# powersupplyboard.net
KiCad netlist of a schematic drawn in EAGLE
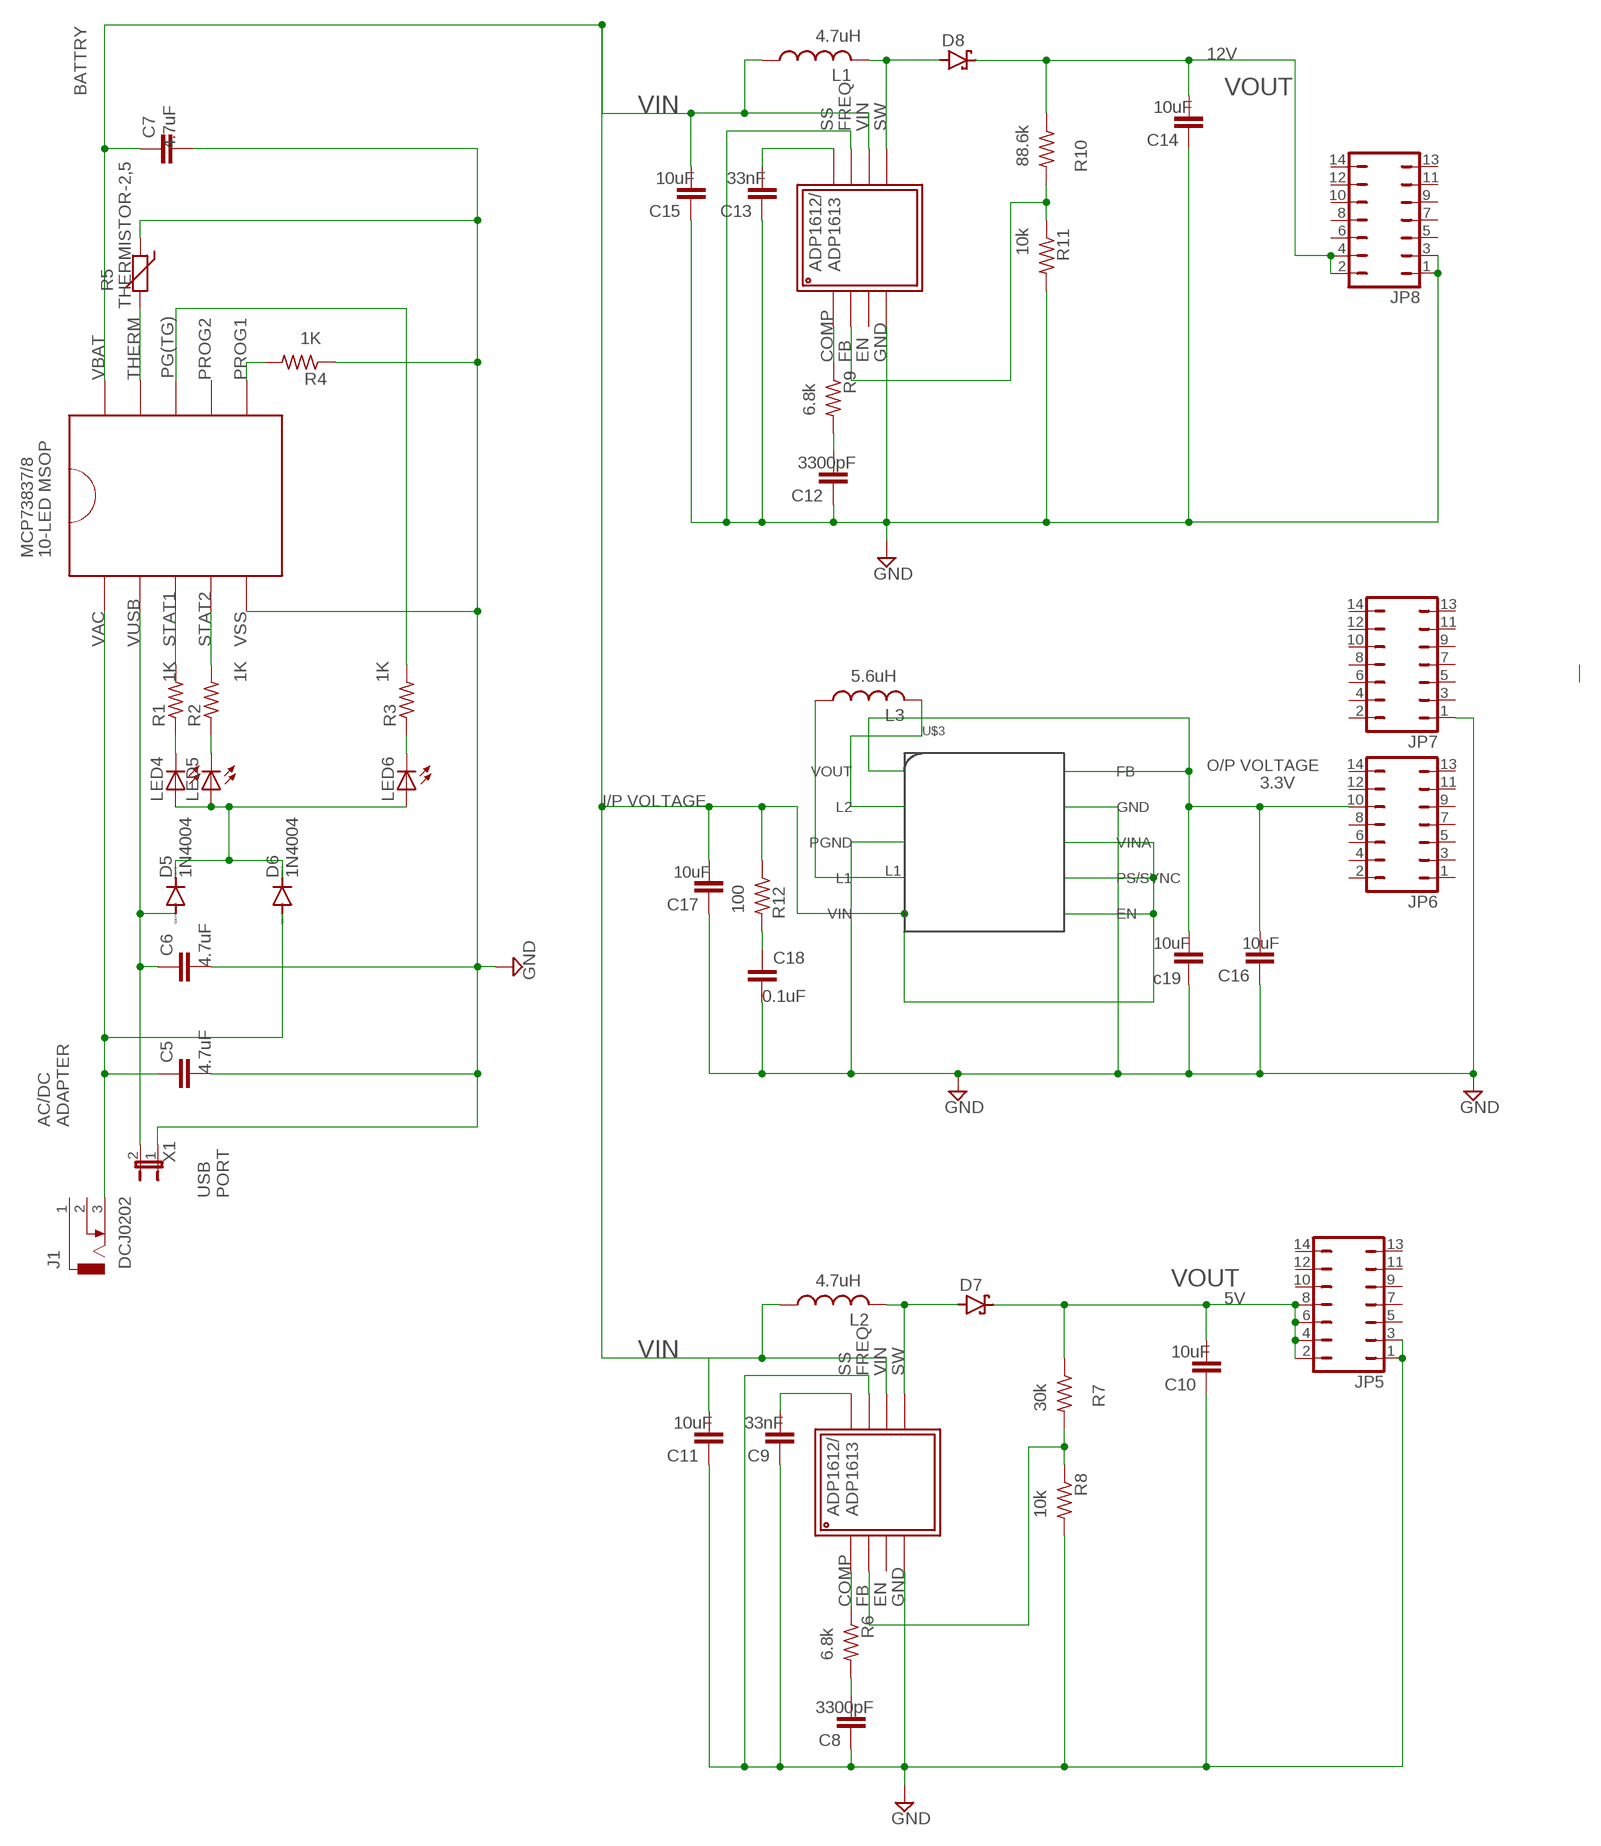
[diagram p0: schematic, sheet 1]

(export (version "E")
  (design (tool "Eeschema 10.0.6"))
  (components
    (comp (ref "C1")
      (value "C2,5-3")
      (footprint "eagle-import:C2.5-3")
      (libsource (lib "eagle-import") (part "C2,5-3"))
    )
    (comp (ref "C5")
      (value "C2.5/5")
      (footprint "eagle-import:C2.5-5")
      (libsource (lib "eagle-import") (part "C2.5/5"))
    )
    (comp (ref "C6")
      (value "C2.5/5")
      (footprint "eagle-import:C2.5-5")
      (libsource (lib "eagle-import") (part "C2.5/5"))
    )
    (comp (ref "C7")
      (value "C2.5/5")
      (footprint "eagle-import:C2.5-5")
      (libsource (lib "eagle-import") (part "C2.5/5"))
    )
    (comp (ref "C8")
      (value "C2,5-3")
      (footprint "eagle-import:C2.5-3")
      (libsource (lib "eagle-import") (part "C2,5-3"))
    )
    (comp (ref "C9")
      (value "C2,5-3")
      (footprint "eagle-import:C2.5-3")
      (libsource (lib "eagle-import") (part "C2,5-3"))
    )
    (comp (ref "C10")
      (value "C2,5-3")
      (footprint "eagle-import:C2.5-3")
      (libsource (lib "eagle-import") (part "C2,5-3"))
    )
    (comp (ref "C11")
      (value "C2,5-3")
      (footprint "eagle-import:C2.5-3")
      (libsource (lib "eagle-import") (part "C2,5-3"))
    )
    (comp (ref "C12")
      (value "C2,5-3")
      (footprint "eagle-import:C2.5-3")
      (libsource (lib "eagle-import") (part "C2,5-3"))
    )
    (comp (ref "C13")
      (value "C2,5-3")
      (footprint "eagle-import:C2.5-3")
      (libsource (lib "eagle-import") (part "C2,5-3"))
    )
    (comp (ref "C14")
      (value "C2,5-3")
      (footprint "eagle-import:C2.5-3")
      (libsource (lib "eagle-import") (part "C2,5-3"))
    )
    (comp (ref "C15")
      (value "C2,5-3")
      (footprint "eagle-import:C2.5-3")
      (libsource (lib "eagle-import") (part "C2,5-3"))
    )
    (comp (ref "C16")
      (value "C2,5-3")
      (footprint "eagle-import:C2.5-3")
      (libsource (lib "eagle-import") (part "C2,5-3"))
    )
    (comp (ref "C17")
      (value "C2,5-3")
      (footprint "eagle-import:C2.5-3")
      (libsource (lib "eagle-import") (part "C2,5-3"))
    )
    (comp (ref "C18")
      (value "C2,5-3")
      (footprint "eagle-import:C2.5-3")
      (libsource (lib "eagle-import") (part "C2,5-3"))
    )
    (comp (ref "D5")
      (value "1N4004")
      (footprint "eagle-import:DO41-10")
      (libsource (lib "eagle-import") (part "1N4004"))
    )
    (comp (ref "D6")
      (value "1N4004")
      (footprint "eagle-import:DO41-10")
      (libsource (lib "eagle-import") (part "1N4004"))
    )
    (comp (ref "D7")
      (value "SCHOTTKY-DIODEC4111-15")
      (footprint "eagle-import:C4111-15")
      (libsource (lib "eagle-import") (part "SCHOTTKY-DIODEC4111-15"))
    )
    (comp (ref "D8")
      (value "SCHOTTKY-DIODEC4111-15")
      (footprint "eagle-import:C4111-15")
      (libsource (lib "eagle-import") (part "SCHOTTKY-DIODEC4111-15"))
    )
    (comp (ref "J1")
      (value "DCJ0202")
      (footprint "eagle-import:DCJ0202")
      (libsource (lib "eagle-import") (part "DCJ0202"))
    )
    (comp (ref "JP1")
      (value "JP1E")
      (footprint "eagle-import:JP1")
      (libsource (lib "eagle-import") (part "JP1E"))
    )
    (comp (ref "JP5")
      (value "JP7Q")
      (footprint "eagle-import:JP7Q")
      (libsource (lib "eagle-import") (part "JP7Q"))
    )
    (comp (ref "JP6")
      (value "JP7Q")
      (footprint "eagle-import:JP7Q")
      (libsource (lib "eagle-import") (part "JP7Q"))
    )
    (comp (ref "JP7")
      (value "JP7Q")
      (footprint "eagle-import:JP7Q")
      (libsource (lib "eagle-import") (part "JP7Q"))
    )
    (comp (ref "JP8")
      (value "JP7Q")
      (footprint "eagle-import:JP7Q")
      (libsource (lib "eagle-import") (part "JP7Q"))
    )
    (comp (ref "L1")
      (value "L-US0204/5")
      (footprint "eagle-import:0204_5")
      (libsource (lib "eagle-import") (part "L-US0204/5"))
    )
    (comp (ref "L2")
      (value "L-US0204/5")
      (footprint "eagle-import:0204_5")
      (libsource (lib "eagle-import") (part "L-US0204/5"))
    )
    (comp (ref "L3")
      (value "L-US0204/5")
      (footprint "eagle-import:0204_5")
      (libsource (lib "eagle-import") (part "L-US0204/5"))
    )
    (comp (ref "LED4")
      (value "LED3MM")
      (footprint "eagle-import:LED3MM")
      (libsource (lib "eagle-import") (part "LED3MM"))
    )
    (comp (ref "LED5")
      (value "LED3MM")
      (footprint "eagle-import:LED3MM")
      (libsource (lib "eagle-import") (part "LED3MM"))
    )
    (comp (ref "LED6")
      (value "LED3MM")
      (footprint "eagle-import:LED3MM")
      (libsource (lib "eagle-import") (part "LED3MM"))
    )
    (comp (ref "R1")
      (value "R-US_0204/2V")
      (footprint "eagle-import:0204V")
      (libsource (lib "eagle-import") (part "R-US_0204/2V"))
    )
    (comp (ref "R2")
      (value "R-US_0204/2V")
      (footprint "eagle-import:0204V")
      (libsource (lib "eagle-import") (part "R-US_0204/2V"))
    )
    (comp (ref "R3")
      (value "R-US_0204/2V")
      (footprint "eagle-import:0204V")
      (libsource (lib "eagle-import") (part "R-US_0204/2V"))
    )
    (comp (ref "R4")
      (value "R-US_0204/2V")
      (footprint "eagle-import:0204V")
      (libsource (lib "eagle-import") (part "R-US_0204/2V"))
    )
    (comp (ref "R5")
      (value "THERMISTOR-2,5")
      (footprint "eagle-import:RS-2,5")
      (libsource (lib "eagle-import") (part "THERMISTOR-2,5"))
    )
    (comp (ref "R6")
      (value "R-US_0204/2V")
      (footprint "eagle-import:0204V")
      (libsource (lib "eagle-import") (part "R-US_0204/2V"))
    )
    (comp (ref "R7")
      (value "R-US_0204/2V")
      (footprint "eagle-import:0204V")
      (libsource (lib "eagle-import") (part "R-US_0204/2V"))
    )
    (comp (ref "R8")
      (value "R-US_0204/2V")
      (footprint "eagle-import:0204V")
      (libsource (lib "eagle-import") (part "R-US_0204/2V"))
    )
    (comp (ref "R9")
      (value "R-US_0204/2V")
      (footprint "eagle-import:0204V")
      (libsource (lib "eagle-import") (part "R-US_0204/2V"))
    )
    (comp (ref "R10")
      (value "R-US_0204/2V")
      (footprint "eagle-import:0204V")
      (libsource (lib "eagle-import") (part "R-US_0204/2V"))
    )
    (comp (ref "R11")
      (value "R-US_0204/2V")
      (footprint "eagle-import:0204V")
      (libsource (lib "eagle-import") (part "R-US_0204/2V"))
    )
    (comp (ref "R12")
      (value "R-US_0204/2V")
      (footprint "eagle-import:0204V")
      (libsource (lib "eagle-import") (part "R-US_0204/2V"))
    )
    (comp (ref "U$1")
      (value "ADP1612")
      (footprint "eagle-import:ADP1612")
      (libsource (lib "eagle-import") (part "ADP1612"))
    )
    (comp (ref "U$2")
      (value "ADP1612")
      (footprint "eagle-import:ADP1612")
      (libsource (lib "eagle-import") (part "ADP1612"))
    )
    (comp (ref "U$3")
      (value "TPS63002")
      (footprint "eagle-import:TPS63002")
      (libsource (lib "eagle-import") (part "TPS63002"))
    )
    (comp (ref "U$4")
      (value "MCP73837/8")
      (footprint "eagle-import:MCP73837_8")
      (libsource (lib "eagle-import") (part "MCP73837/8"))
    )
  )
  (nets
    (net (code "1") (name "GND") (class "Default")
      (node (ref "C1") (pin "1") (pinfunction "1_1") (pintype "passive"))
      (node (ref "C10") (pin "1") (pinfunction "1_1") (pintype "passive"))
      (node (ref "C11") (pin "1") (pinfunction "1_1") (pintype "passive"))
      (node (ref "C12") (pin "1") (pinfunction "1_1") (pintype "passive"))
      (node (ref "C13") (pin "1") (pinfunction "1_1") (pintype "passive"))
      (node (ref "C14") (pin "1") (pinfunction "1_1") (pintype "passive"))
      (node (ref "C15") (pin "1") (pinfunction "1_1") (pintype "passive"))
      (node (ref "C16") (pin "1") (pinfunction "1_1") (pintype "passive"))
      (node (ref "C17") (pin "1") (pinfunction "1_1") (pintype "passive"))
      (node (ref "C18") (pin "2") (pinfunction "2_2") (pintype "passive"))
      (node (ref "C5") (pin "2") (pinfunction "2_2") (pintype "passive"))
      (node (ref "C6") (pin "2") (pinfunction "2_2") (pintype "passive"))
      (node (ref "C7") (pin "2") (pinfunction "2_2") (pintype "passive"))
      (node (ref "C8") (pin "1") (pinfunction "1_1") (pintype "passive"))
      (node (ref "C9") (pin "1") (pinfunction "1_1") (pintype "passive"))
      (node (ref "JP1") (pin "1") (pinfunction "1_1") (pintype "passive"))
      (node (ref "JP5") (pin "1") (pinfunction "1_1") (pintype "passive"))
      (node (ref "JP5") (pin "3") (pinfunction "3_3") (pintype "passive"))
      (node (ref "JP7") (pin "1") (pinfunction "1_1") (pintype "passive"))
      (node (ref "JP8") (pin "1") (pinfunction "1_1") (pintype "passive"))
      (node (ref "JP8") (pin "3") (pinfunction "3_3") (pintype "passive"))
      (node (ref "R11") (pin "2") (pinfunction "2_2") (pintype "passive"))
      (node (ref "R4") (pin "1") (pinfunction "1_1") (pintype "passive"))
      (node (ref "R5") (pin "1") (pinfunction "1_1") (pintype "passive"))
      (node (ref "R8") (pin "2") (pinfunction "2_2") (pintype "passive"))
      (node (ref "U$1") (pin "P$4") (pinfunction "P$4_P$4") (pintype "bidirectional"))
      (node (ref "U$1") (pin "P$6") (pinfunction "P$6_P$6") (pintype "bidirectional"))
      (node (ref "U$2") (pin "P$4") (pinfunction "P$4_P$4") (pintype "bidirectional"))
      (node (ref "U$2") (pin "P$6") (pinfunction "P$6_P$6") (pintype "bidirectional"))
      (node (ref "U$3") (pin "GND") (pinfunction "GND_GND") (pintype "bidirectional"))
      (node (ref "U$3") (pin "PGND") (pinfunction "PGND_PGND") (pintype "bidirectional"))
      (node (ref "U$4") (pin "P$5") (pinfunction "P$5_P$5") (pintype "bidirectional"))
    )
    (net (code "2") (name "Net-(C1-Pad2)") (class "Default")
      (node (ref "C1") (pin "2") (pinfunction "2_2") (pintype "passive"))
      (node (ref "C16") (pin "2") (pinfunction "2_2") (pintype "passive"))
      (node (ref "JP6") (pin "10") (pinfunction "10_10") (pintype "passive"))
      (node (ref "U$3") (pin "FB") (pinfunction "FB_FB") (pintype "bidirectional"))
      (node (ref "U$3") (pin "VOUT") (pinfunction "VOUT_VOUT") (pintype "bidirectional"))
    )
    (net (code "3") (name "Net-(C5-Pad1)") (class "Default")
      (node (ref "C5") (pin "1") (pinfunction "1_1") (pintype "passive"))
      (node (ref "D6") (pin "A") (pinfunction "A_A") (pintype "passive"))
      (node (ref "J1") (pin "3") (pinfunction "3_3") (pintype "passive"))
      (node (ref "U$4") (pin "P$1") (pinfunction "P$1_P$1") (pintype "bidirectional"))
    )
    (net (code "4") (name "Net-(C6-Pad1)") (class "Default")
      (node (ref "C6") (pin "1") (pinfunction "1_1") (pintype "passive"))
      (node (ref "D5") (pin "A") (pinfunction "A_A") (pintype "passive"))
      (node (ref "JP1") (pin "2") (pinfunction "2_2") (pintype "passive"))
      (node (ref "U$4") (pin "P$2") (pinfunction "P$2_P$2") (pintype "bidirectional"))
    )
    (net (code "5") (name "Net-(C8-Pad2)") (class "Default")
      (node (ref "C8") (pin "2") (pinfunction "2_2") (pintype "passive"))
      (node (ref "R6") (pin "2") (pinfunction "2_2") (pintype "passive"))
    )
    (net (code "6") (name "Net-(C9-Pad2)") (class "Default")
      (node (ref "C9") (pin "2") (pinfunction "2_2") (pintype "passive"))
      (node (ref "U$1") (pin "P$5") (pinfunction "P$5_P$5") (pintype "bidirectional"))
    )
    (net (code "7") (name "Net-(C10-Pad2)") (class "Default")
      (node (ref "C10") (pin "2") (pinfunction "2_2") (pintype "passive"))
      (node (ref "D7") (pin "C") (pinfunction "C_C") (pintype "passive"))
      (node (ref "JP5") (pin "2") (pinfunction "2_2") (pintype "passive"))
      (node (ref "JP5") (pin "4") (pinfunction "4_4") (pintype "passive"))
      (node (ref "JP5") (pin "6") (pinfunction "6_6") (pintype "passive"))
      (node (ref "JP5") (pin "8") (pinfunction "8_8") (pintype "passive"))
      (node (ref "R7") (pin "1") (pinfunction "1_1") (pintype "passive"))
    )
    (net (code "8") (name "Net-(C11-Pad2)") (class "Default")
      (node (ref "C11") (pin "2") (pinfunction "2_2") (pintype "passive"))
      (node (ref "C15") (pin "2") (pinfunction "2_2") (pintype "passive"))
      (node (ref "C17") (pin "2") (pinfunction "2_2") (pintype "passive"))
      (node (ref "C7") (pin "1") (pinfunction "1_1") (pintype "passive"))
      (node (ref "L1") (pin "1") (pinfunction "1_1") (pintype "passive"))
      (node (ref "L2") (pin "1") (pinfunction "1_1") (pintype "passive"))
      (node (ref "R12") (pin "1") (pinfunction "1_1") (pintype "passive"))
      (node (ref "U$1") (pin "P$7") (pinfunction "P$7_P$7") (pintype "bidirectional"))
      (node (ref "U$2") (pin "P$7") (pinfunction "P$7_P$7") (pintype "bidirectional"))
      (node (ref "U$3") (pin "EN") (pinfunction "EN_EN") (pintype "bidirectional"))
      (node (ref "U$3") (pin "PS/SYNC") (pinfunction "PS/SYNC_PS/SYNC") (pintype "bidirectional"))
      (node (ref "U$3") (pin "VIN") (pinfunction "VIN_VIN") (pintype "bidirectional"))
      (node (ref "U$3") (pin "VINA") (pinfunction "VINA_VINA") (pintype "bidirectional"))
      (node (ref "U$4") (pin "P$10") (pinfunction "P$10_P$10") (pintype "bidirectional"))
    )
    (net (code "9") (name "Net-(C12-Pad2)") (class "Default")
      (node (ref "C12") (pin "2") (pinfunction "2_2") (pintype "passive"))
      (node (ref "R9") (pin "2") (pinfunction "2_2") (pintype "passive"))
    )
    (net (code "10") (name "Net-(C13-Pad2)") (class "Default")
      (node (ref "C13") (pin "2") (pinfunction "2_2") (pintype "passive"))
      (node (ref "U$2") (pin "P$5") (pinfunction "P$5_P$5") (pintype "bidirectional"))
    )
    (net (code "11") (name "Net-(C14-Pad2)") (class "Default")
      (node (ref "C14") (pin "2") (pinfunction "2_2") (pintype "passive"))
      (node (ref "D8") (pin "C") (pinfunction "C_C") (pintype "passive"))
      (node (ref "JP8") (pin "2") (pinfunction "2_2") (pintype "passive"))
      (node (ref "JP8") (pin "4") (pinfunction "4_4") (pintype "passive"))
      (node (ref "R10") (pin "1") (pinfunction "1_1") (pintype "passive"))
    )
    (net (code "12") (name "Net-(C18-Pad1)") (class "Default")
      (node (ref "C18") (pin "1") (pinfunction "1_1") (pintype "passive"))
      (node (ref "R12") (pin "2") (pinfunction "2_2") (pintype "passive"))
    )
    (net (code "13") (name "Net-(D5-PadC)") (class "Default")
      (node (ref "D5") (pin "C") (pinfunction "C_C") (pintype "passive"))
      (node (ref "D6") (pin "C") (pinfunction "C_C") (pintype "passive"))
      (node (ref "LED4") (pin "A") (pinfunction "A_A") (pintype "passive"))
      (node (ref "LED5") (pin "A") (pinfunction "A_A") (pintype "passive"))
      (node (ref "LED6") (pin "A") (pinfunction "A_A") (pintype "passive"))
    )
    (net (code "14") (name "Net-(D7-PadA)") (class "Default")
      (node (ref "D7") (pin "A") (pinfunction "A_A") (pintype "passive"))
      (node (ref "L2") (pin "2") (pinfunction "2_2") (pintype "passive"))
      (node (ref "U$1") (pin "P$8") (pinfunction "P$8_P$8") (pintype "bidirectional"))
    )
    (net (code "15") (name "Net-(D8-PadA)") (class "Default")
      (node (ref "D8") (pin "A") (pinfunction "A_A") (pintype "passive"))
      (node (ref "L1") (pin "2") (pinfunction "2_2") (pintype "passive"))
      (node (ref "U$2") (pin "P$8") (pinfunction "P$8_P$8") (pintype "bidirectional"))
    )
    (net (code "16") (name "Net-(L3-Pad1)") (class "Default")
      (node (ref "L3") (pin "1") (pinfunction "1_1") (pintype "passive"))
      (node (ref "U$3") (pin "L1") (pinfunction "L1_L1") (pintype "bidirectional"))
    )
    (net (code "17") (name "Net-(L3-Pad2)") (class "Default")
      (node (ref "L3") (pin "2") (pinfunction "2_2") (pintype "passive"))
      (node (ref "U$3") (pin "L2") (pinfunction "L2_L2") (pintype "bidirectional"))
    )
    (net (code "18") (name "Net-(LED4-C)") (class "Default")
      (node (ref "LED4") (pin "K") (pinfunction "C_K") (pintype "passive"))
      (node (ref "R1") (pin "1") (pinfunction "1_1") (pintype "passive"))
    )
    (net (code "19") (name "Net-(LED5-C)") (class "Default")
      (node (ref "LED5") (pin "K") (pinfunction "C_K") (pintype "passive"))
      (node (ref "R2") (pin "1") (pinfunction "1_1") (pintype "passive"))
    )
    (net (code "20") (name "Net-(LED6-C)") (class "Default")
      (node (ref "LED6") (pin "K") (pinfunction "C_K") (pintype "passive"))
      (node (ref "R3") (pin "1") (pinfunction "1_1") (pintype "passive"))
    )
    (net (code "21") (name "Net-(R1-Pad2)") (class "Default")
      (node (ref "R1") (pin "2") (pinfunction "2_2") (pintype "passive"))
      (node (ref "U$4") (pin "P$3") (pinfunction "P$3_P$3") (pintype "bidirectional"))
    )
    (net (code "22") (name "Net-(R2-Pad2)") (class "Default")
      (node (ref "R2") (pin "2") (pinfunction "2_2") (pintype "passive"))
      (node (ref "U$4") (pin "P$4") (pinfunction "P$4_P$4") (pintype "bidirectional"))
    )
    (net (code "23") (name "Net-(R3-Pad2)") (class "Default")
      (node (ref "R3") (pin "2") (pinfunction "2_2") (pintype "passive"))
      (node (ref "U$4") (pin "P$8") (pinfunction "P$8_P$8") (pintype "bidirectional"))
    )
    (net (code "24") (name "Net-(R4-Pad2)") (class "Default")
      (node (ref "R4") (pin "2") (pinfunction "2_2") (pintype "passive"))
      (node (ref "U$4") (pin "P$6") (pinfunction "P$6_P$6") (pintype "bidirectional"))
    )
    (net (code "25") (name "Net-(R5-Pad2)") (class "Default")
      (node (ref "R5") (pin "2") (pinfunction "2_2") (pintype "passive"))
      (node (ref "U$4") (pin "P$9") (pinfunction "P$9_P$9") (pintype "bidirectional"))
    )
    (net (code "26") (name "Net-(R6-Pad1)") (class "Default")
      (node (ref "R6") (pin "1") (pinfunction "1_1") (pintype "passive"))
      (node (ref "U$1") (pin "P$1") (pinfunction "P$1_P$1") (pintype "bidirectional"))
    )
    (net (code "27") (name "Net-(R7-Pad2)") (class "Default")
      (node (ref "R7") (pin "2") (pinfunction "2_2") (pintype "passive"))
      (node (ref "R8") (pin "1") (pinfunction "1_1") (pintype "passive"))
      (node (ref "U$1") (pin "P$2") (pinfunction "P$2_P$2") (pintype "bidirectional"))
    )
    (net (code "28") (name "Net-(R9-Pad1)") (class "Default")
      (node (ref "R9") (pin "1") (pinfunction "1_1") (pintype "passive"))
      (node (ref "U$2") (pin "P$1") (pinfunction "P$1_P$1") (pintype "bidirectional"))
    )
    (net (code "29") (name "Net-(R10-Pad2)") (class "Default")
      (node (ref "R10") (pin "2") (pinfunction "2_2") (pintype "passive"))
      (node (ref "R11") (pin "1") (pinfunction "1_1") (pintype "passive"))
      (node (ref "U$2") (pin "P$2") (pinfunction "P$2_P$2") (pintype "bidirectional"))
    )
    (net (code "30") (name "unconnected-(J1-Pad1)") (class "Default")
      (node (ref "J1") (pin "1") (pinfunction "1_1") (pintype "passive"))
    )
    (net (code "31") (name "unconnected-(J1-Pad2)") (class "Default")
      (node (ref "J1") (pin "2") (pinfunction "2_2") (pintype "passive"))
    )
    (net (code "32") (name "unconnected-(JP5-Pad5)") (class "Default")
      (node (ref "JP5") (pin "5") (pinfunction "5_5") (pintype "passive"))
    )
    (net (code "33") (name "unconnected-(JP5-Pad7)") (class "Default")
      (node (ref "JP5") (pin "7") (pinfunction "7_7") (pintype "passive"))
    )
    (net (code "34") (name "unconnected-(JP5-Pad9)") (class "Default")
      (node (ref "JP5") (pin "9") (pinfunction "9_9") (pintype "passive"))
    )
    (net (code "35") (name "unconnected-(JP5-Pad10)") (class "Default")
      (node (ref "JP5") (pin "10") (pinfunction "10_10") (pintype "passive"))
    )
    (net (code "36") (name "unconnected-(JP5-Pad11)") (class "Default")
      (node (ref "JP5") (pin "11") (pinfunction "11_11") (pintype "passive"))
    )
    (net (code "37") (name "unconnected-(JP5-Pad12)") (class "Default")
      (node (ref "JP5") (pin "12") (pinfunction "12_12") (pintype "passive"))
    )
    (net (code "38") (name "unconnected-(JP5-Pad13)") (class "Default")
      (node (ref "JP5") (pin "13") (pinfunction "13_13") (pintype "passive"))
    )
    (net (code "39") (name "unconnected-(JP5-Pad14)") (class "Default")
      (node (ref "JP5") (pin "14") (pinfunction "14_14") (pintype "passive"))
    )
    (net (code "40") (name "unconnected-(JP6-Pad1)") (class "Default")
      (node (ref "JP6") (pin "1") (pinfunction "1_1") (pintype "passive"))
    )
    (net (code "41") (name "unconnected-(JP6-Pad2)") (class "Default")
      (node (ref "JP6") (pin "2") (pinfunction "2_2") (pintype "passive"))
    )
    (net (code "42") (name "unconnected-(JP6-Pad3)") (class "Default")
      (node (ref "JP6") (pin "3") (pinfunction "3_3") (pintype "passive"))
    )
    (net (code "43") (name "unconnected-(JP6-Pad4)") (class "Default")
      (node (ref "JP6") (pin "4") (pinfunction "4_4") (pintype "passive"))
    )
    (net (code "44") (name "unconnected-(JP6-Pad5)") (class "Default")
      (node (ref "JP6") (pin "5") (pinfunction "5_5") (pintype "passive"))
    )
    (net (code "45") (name "unconnected-(JP6-Pad6)") (class "Default")
      (node (ref "JP6") (pin "6") (pinfunction "6_6") (pintype "passive"))
    )
    (net (code "46") (name "unconnected-(JP6-Pad7)") (class "Default")
      (node (ref "JP6") (pin "7") (pinfunction "7_7") (pintype "passive"))
    )
    (net (code "47") (name "unconnected-(JP6-Pad8)") (class "Default")
      (node (ref "JP6") (pin "8") (pinfunction "8_8") (pintype "passive"))
    )
    (net (code "48") (name "unconnected-(JP6-Pad9)") (class "Default")
      (node (ref "JP6") (pin "9") (pinfunction "9_9") (pintype "passive"))
    )
    (net (code "49") (name "unconnected-(JP6-Pad11)") (class "Default")
      (node (ref "JP6") (pin "11") (pinfunction "11_11") (pintype "passive"))
    )
    (net (code "50") (name "unconnected-(JP6-Pad12)") (class "Default")
      (node (ref "JP6") (pin "12") (pinfunction "12_12") (pintype "passive"))
    )
    (net (code "51") (name "unconnected-(JP6-Pad13)") (class "Default")
      (node (ref "JP6") (pin "13") (pinfunction "13_13") (pintype "passive"))
    )
    (net (code "52") (name "unconnected-(JP6-Pad14)") (class "Default")
      (node (ref "JP6") (pin "14") (pinfunction "14_14") (pintype "passive"))
    )
    (net (code "53") (name "unconnected-(JP7-Pad2)") (class "Default")
      (node (ref "JP7") (pin "2") (pinfunction "2_2") (pintype "passive"))
    )
    (net (code "54") (name "unconnected-(JP7-Pad3)") (class "Default")
      (node (ref "JP7") (pin "3") (pinfunction "3_3") (pintype "passive"))
    )
    (net (code "55") (name "unconnected-(JP7-Pad4)") (class "Default")
      (node (ref "JP7") (pin "4") (pinfunction "4_4") (pintype "passive"))
    )
    (net (code "56") (name "unconnected-(JP7-Pad5)") (class "Default")
      (node (ref "JP7") (pin "5") (pinfunction "5_5") (pintype "passive"))
    )
    (net (code "57") (name "unconnected-(JP7-Pad6)") (class "Default")
      (node (ref "JP7") (pin "6") (pinfunction "6_6") (pintype "passive"))
    )
    (net (code "58") (name "unconnected-(JP7-Pad7)") (class "Default")
      (node (ref "JP7") (pin "7") (pinfunction "7_7") (pintype "passive"))
    )
    (net (code "59") (name "unconnected-(JP7-Pad8)") (class "Default")
      (node (ref "JP7") (pin "8") (pinfunction "8_8") (pintype "passive"))
    )
    (net (code "60") (name "unconnected-(JP7-Pad9)") (class "Default")
      (node (ref "JP7") (pin "9") (pinfunction "9_9") (pintype "passive"))
    )
    (net (code "61") (name "unconnected-(JP7-Pad10)") (class "Default")
      (node (ref "JP7") (pin "10") (pinfunction "10_10") (pintype "passive"))
    )
    (net (code "62") (name "unconnected-(JP7-Pad11)") (class "Default")
      (node (ref "JP7") (pin "11") (pinfunction "11_11") (pintype "passive"))
    )
    (net (code "63") (name "unconnected-(JP7-Pad12)") (class "Default")
      (node (ref "JP7") (pin "12") (pinfunction "12_12") (pintype "passive"))
    )
    (net (code "64") (name "unconnected-(JP7-Pad13)") (class "Default")
      (node (ref "JP7") (pin "13") (pinfunction "13_13") (pintype "passive"))
    )
    (net (code "65") (name "unconnected-(JP7-Pad14)") (class "Default")
      (node (ref "JP7") (pin "14") (pinfunction "14_14") (pintype "passive"))
    )
    (net (code "66") (name "unconnected-(JP8-Pad5)") (class "Default")
      (node (ref "JP8") (pin "5") (pinfunction "5_5") (pintype "passive"))
    )
    (net (code "67") (name "unconnected-(JP8-Pad6)") (class "Default")
      (node (ref "JP8") (pin "6") (pinfunction "6_6") (pintype "passive"))
    )
    (net (code "68") (name "unconnected-(JP8-Pad7)") (class "Default")
      (node (ref "JP8") (pin "7") (pinfunction "7_7") (pintype "passive"))
    )
    (net (code "69") (name "unconnected-(JP8-Pad8)") (class "Default")
      (node (ref "JP8") (pin "8") (pinfunction "8_8") (pintype "passive"))
    )
    (net (code "70") (name "unconnected-(JP8-Pad9)") (class "Default")
      (node (ref "JP8") (pin "9") (pinfunction "9_9") (pintype "passive"))
    )
    (net (code "71") (name "unconnected-(JP8-Pad10)") (class "Default")
      (node (ref "JP8") (pin "10") (pinfunction "10_10") (pintype "passive"))
    )
    (net (code "72") (name "unconnected-(JP8-Pad11)") (class "Default")
      (node (ref "JP8") (pin "11") (pinfunction "11_11") (pintype "passive"))
    )
    (net (code "73") (name "unconnected-(JP8-Pad12)") (class "Default")
      (node (ref "JP8") (pin "12") (pinfunction "12_12") (pintype "passive"))
    )
    (net (code "74") (name "unconnected-(JP8-Pad13)") (class "Default")
      (node (ref "JP8") (pin "13") (pinfunction "13_13") (pintype "passive"))
    )
    (net (code "75") (name "unconnected-(JP8-Pad14)") (class "Default")
      (node (ref "JP8") (pin "14") (pinfunction "14_14") (pintype "passive"))
    )
    (net (code "76") (name "unconnected-(U$1-PadP$3)") (class "Default")
      (node (ref "U$1") (pin "P$3") (pinfunction "P$3_P$3") (pintype "bidirectional"))
    )
    (net (code "77") (name "unconnected-(U$2-PadP$3)") (class "Default")
      (node (ref "U$2") (pin "P$3") (pinfunction "P$3_P$3") (pintype "bidirectional"))
    )
    (net (code "78") (name "unconnected-(U$4-PadP$7)") (class "Default")
      (node (ref "U$4") (pin "P$7") (pinfunction "P$7_P$7") (pintype "bidirectional"))
    )
  )
)
